# Slave.net
KiCad netlist of a schematic drawn in EAGLE
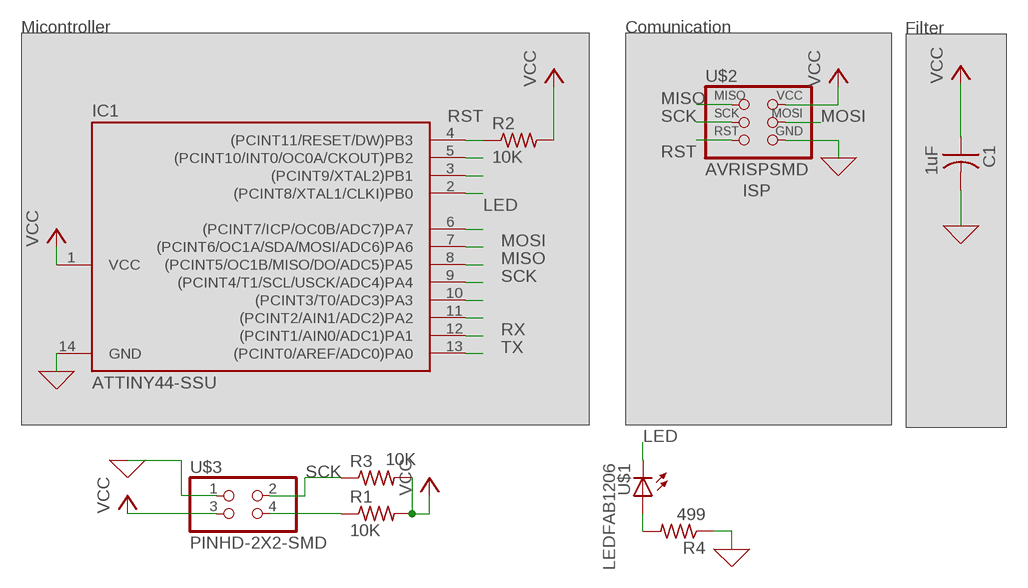
[diagram p0: schematic, sheet 1]

(export (version "E")
  (design (tool "Eeschema 10.0.6"))
  (components
    (comp (ref "C1")
      (value "1uF")
      (footprint "eagle-import:C1206FAB")
      (libsource (lib "eagle-import") (part "CAP-US1206FAB"))
    )
    (comp (ref "IC1")
      (value "ATTINY44-SSU")
      (footprint "eagle-import:SOIC14")
      (libsource (lib "eagle-import") (part "ATTINY44-SSU"))
    )
    (comp (ref "R1")
      (value "10K")
      (footprint "eagle-import:R1206FAB")
      (libsource (lib "eagle-import") (part "RES-US1206FAB"))
    )
    (comp (ref "R2")
      (value "10K")
      (footprint "eagle-import:R1206FAB")
      (libsource (lib "eagle-import") (part "RES-US1206FAB"))
    )
    (comp (ref "R3")
      (value "10K")
      (footprint "eagle-import:R1206FAB")
      (libsource (lib "eagle-import") (part "RES-US1206FAB"))
    )
    (comp (ref "R4")
      (value "499")
      (footprint "eagle-import:R1206FAB")
      (libsource (lib "eagle-import") (part "RES-US1206FAB"))
    )
    (comp (ref "U$1")
      (value "LEDFAB1206")
      (footprint "eagle-import:LED1206FAB")
      (libsource (lib "eagle-import") (part "LEDFAB1206"))
    )
    (comp (ref "U$2")
      (value "AVRISPSMD")
      (footprint "eagle-import:2X03SMD")
      (libsource (lib "eagle-import") (part "AVRISPSMD"))
    )
    (comp (ref "U$3")
      (value "PINHD-2X2-SMD")
      (footprint "eagle-import:2X02SMD")
      (libsource (lib "eagle-import") (part "PINHD-2X2-SMD"))
    )
  )
  (nets
    (net (code "1") (name "/LED") (class "Default")
      (node (ref "IC1") (pin "6") (pinfunction "(PCINT7/ICP/OC0B/ADC7)PA7_6") (pintype "bidirectional"))
      (node (ref "U$1") (pin "2") (pinfunction "C_2") (pintype "passive"))
    )
    (net (code "2") (name "/MISO") (class "Default")
      (node (ref "IC1") (pin "8") (pinfunction "(PCINT5/OC1B/MISO/DO/ADC5)PA5_8") (pintype "bidirectional"))
      (node (ref "U$2") (pin "1") (pinfunction "MISO_1") (pintype "passive"))
    )
    (net (code "3") (name "/MOSI") (class "Default")
      (node (ref "IC1") (pin "7") (pinfunction "(PCINT6/OC1A/SDA/MOSI/ADC6)PA6_7") (pintype "bidirectional"))
      (node (ref "R1") (pin "1") (pinfunction "1_1") (pintype "passive"))
      (node (ref "U$2") (pin "4") (pinfunction "MOSI_4") (pintype "passive"))
      (node (ref "U$3") (pin "4") (pinfunction "4_4") (pintype "passive"))
    )
    (net (code "4") (name "/RST") (class "Default")
      (node (ref "IC1") (pin "4") (pinfunction "(PCINT11/RESET/DW)PB3_4") (pintype "bidirectional"))
      (node (ref "R2") (pin "1") (pinfunction "1_1") (pintype "passive"))
      (node (ref "U$2") (pin "5") (pinfunction "RST_5") (pintype "passive"))
    )
    (net (code "5") (name "/RX") (class "Default")
      (node (ref "IC1") (pin "12") (pinfunction "(PCINT1/AIN0/ADC1)PA1_12") (pintype "bidirectional"))
    )
    (net (code "6") (name "/SCK") (class "Default")
      (node (ref "IC1") (pin "9") (pinfunction "(PCINT4/T1/SCL/USCK/ADC4)PA4_9") (pintype "bidirectional"))
      (node (ref "R3") (pin "1") (pinfunction "1_1") (pintype "passive"))
      (node (ref "U$2") (pin "3") (pinfunction "SCK_3") (pintype "passive"))
      (node (ref "U$3") (pin "2") (pinfunction "2_2") (pintype "passive"))
    )
    (net (code "7") (name "/TX") (class "Default")
      (node (ref "IC1") (pin "13") (pinfunction "(PCINT0/AREF/ADC0)PA0_13") (pintype "bidirectional"))
    )
    (net (code "8") (name "GND") (class "Default")
      (node (ref "C1") (pin "2") (pinfunction "2_2") (pintype "passive"))
      (node (ref "IC1") (pin "14") (pinfunction "GND_14") (pintype "power_in"))
      (node (ref "R4") (pin "1") (pinfunction "1_1") (pintype "passive"))
      (node (ref "U$2") (pin "6") (pinfunction "GND_6") (pintype "passive"))
      (node (ref "U$3") (pin "1") (pinfunction "1_1") (pintype "passive"))
    )
    (net (code "9") (name "Net-(U$1-A)") (class "Default")
      (node (ref "R4") (pin "2") (pinfunction "2_2") (pintype "passive"))
      (node (ref "U$1") (pin "1") (pinfunction "A_1") (pintype "passive"))
    )
    (net (code "10") (name "VCC") (class "Default")
      (node (ref "C1") (pin "1") (pinfunction "1_1") (pintype "passive"))
      (node (ref "IC1") (pin "1") (pinfunction "VCC_1") (pintype "power_in"))
      (node (ref "R1") (pin "2") (pinfunction "2_2") (pintype "passive"))
      (node (ref "R2") (pin "2") (pinfunction "2_2") (pintype "passive"))
      (node (ref "R3") (pin "2") (pinfunction "2_2") (pintype "passive"))
      (node (ref "U$2") (pin "2") (pinfunction "VCC_2") (pintype "passive"))
      (node (ref "U$3") (pin "3") (pinfunction "3_3") (pintype "passive"))
    )
    (net (code "11") (name "unconnected-(IC1-(PCINT2{slash}AIN1{slash}ADC2)PA2-Pad11)") (class "Default")
      (node (ref "IC1") (pin "11") (pinfunction "(PCINT2/AIN1/ADC2)PA2_11") (pintype "bidirectional"))
    )
    (net (code "12") (name "unconnected-(IC1-(PCINT3{slash}T0{slash}ADC3)PA3-Pad10)") (class "Default")
      (node (ref "IC1") (pin "10") (pinfunction "(PCINT3/T0/ADC3)PA3_10") (pintype "bidirectional"))
    )
    (net (code "13") (name "unconnected-(IC1-(PCINT8{slash}XTAL1{slash}CLKI)PB0-Pad2)") (class "Default")
      (node (ref "IC1") (pin "2") (pinfunction "(PCINT8/XTAL1/CLKI)PB0_2") (pintype "bidirectional"))
    )
    (net (code "14") (name "unconnected-(IC1-(PCINT9{slash}XTAL2)PB1-Pad3)") (class "Default")
      (node (ref "IC1") (pin "3") (pinfunction "(PCINT9/XTAL2)PB1_3") (pintype "bidirectional"))
    )
    (net (code "15") (name "unconnected-(IC1-(PCINT10{slash}INT0{slash}OC0A{slash}CKOUT)PB2-Pad5)") (class "Default")
      (node (ref "IC1") (pin "5") (pinfunction "(PCINT10/INT0/OC0A/CKOUT)PB2_5") (pintype "bidirectional"))
    )
  )
)
